# TRV_CC110L_V1_0.net
KiCad netlist of a schematic drawn in EAGLE
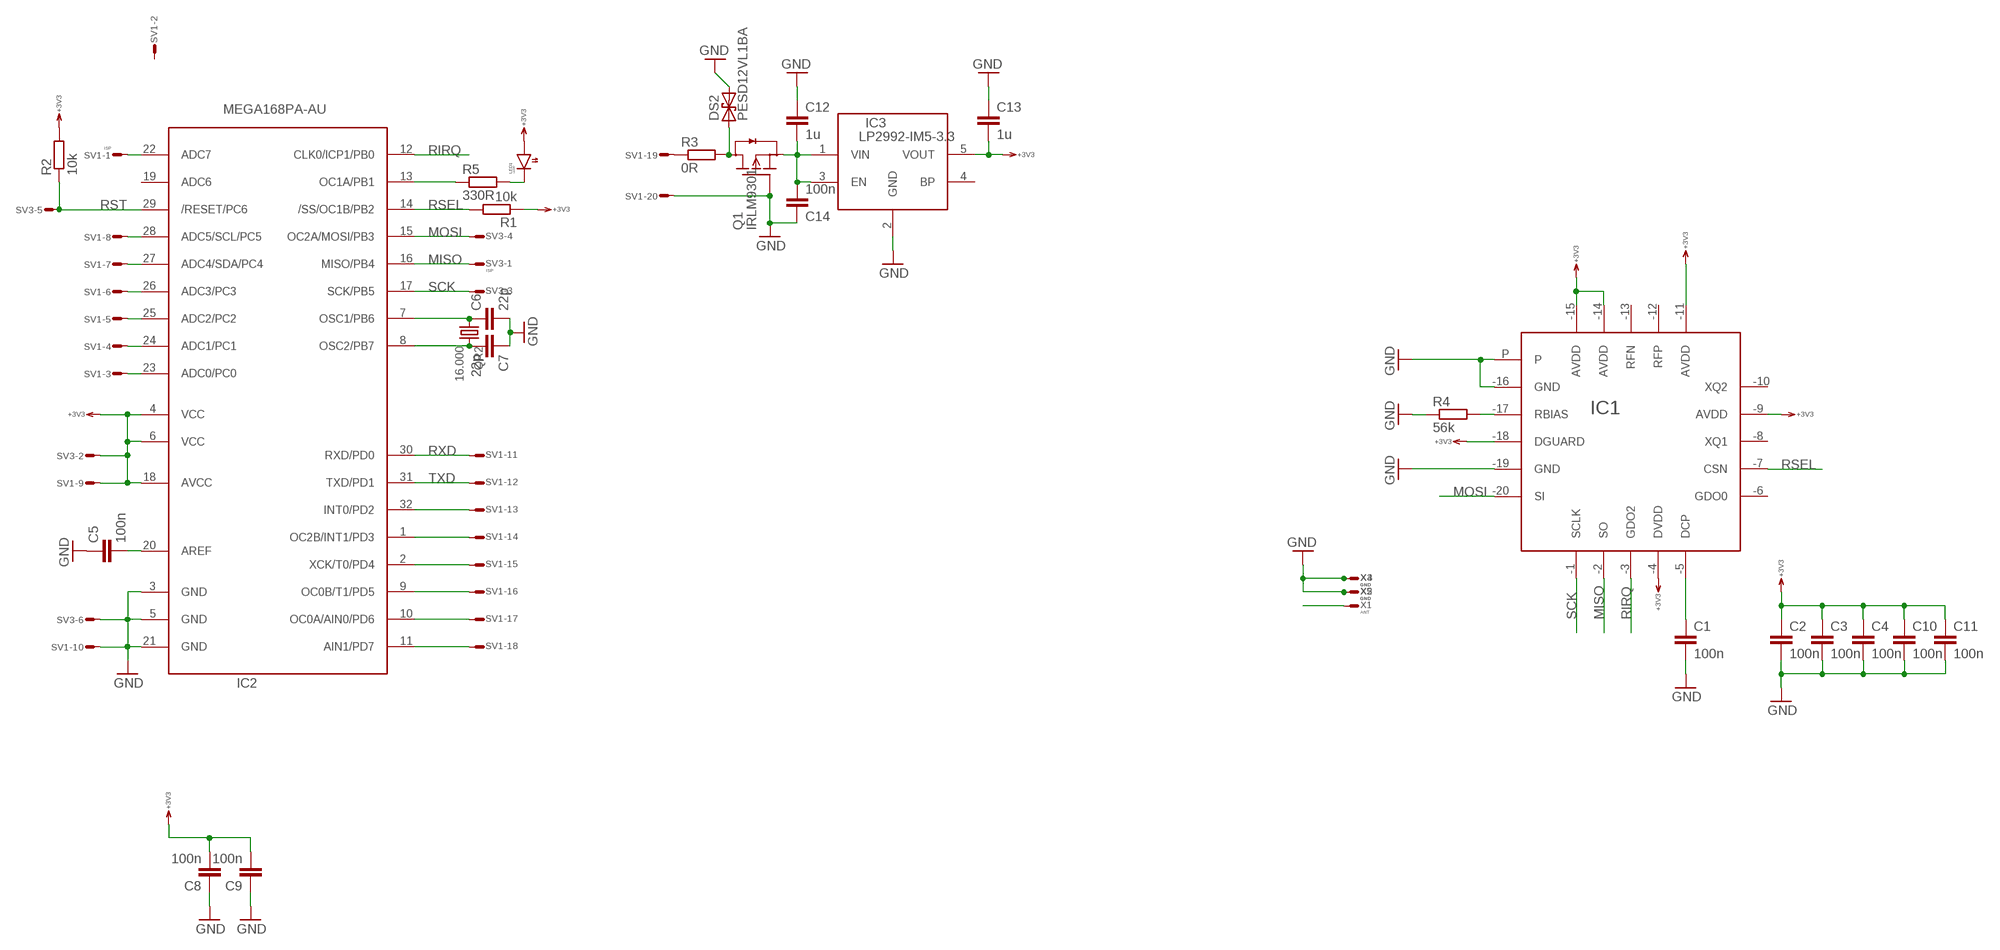
[diagram p0: schematic, sheet 1]

(export (version "E")
  (design (tool "Eeschema 10.0.6"))
  (components
    (comp (ref "C1")
      (value "100n")
      (footprint "eagle-import:0402")
      (libsource (lib "eagle-import") (part "C0402"))
    )
    (comp (ref "C2")
      (value "100n")
      (footprint "eagle-import:0603")
      (libsource (lib "eagle-import") (part "C0603"))
    )
    (comp (ref "C3")
      (value "100n")
      (footprint "eagle-import:0402")
      (libsource (lib "eagle-import") (part "C0402"))
    )
    (comp (ref "C4")
      (value "100n")
      (footprint "eagle-import:0402")
      (libsource (lib "eagle-import") (part "C0402"))
    )
    (comp (ref "C5")
      (value "100n")
      (footprint "eagle-import:0603")
      (libsource (lib "eagle-import") (part "C0603"))
    )
    (comp (ref "C6")
      (value "22p")
      (footprint "eagle-import:0603")
      (libsource (lib "eagle-import") (part "C0603"))
    )
    (comp (ref "C7")
      (value "22p")
      (footprint "eagle-import:0603")
      (libsource (lib "eagle-import") (part "C0603"))
    )
    (comp (ref "C8")
      (value "100n")
      (footprint "eagle-import:0603")
      (libsource (lib "eagle-import") (part "C0603"))
    )
    (comp (ref "C9")
      (value "100n")
      (footprint "eagle-import:0603")
      (libsource (lib "eagle-import") (part "C0603"))
    )
    (comp (ref "C10")
      (value "100n")
      (footprint "eagle-import:0402")
      (libsource (lib "eagle-import") (part "C0402"))
    )
    (comp (ref "C11")
      (value "100n")
      (footprint "eagle-import:0402")
      (libsource (lib "eagle-import") (part "C0402"))
    )
    (comp (ref "C12")
      (value "1u")
      (footprint "eagle-import:0603")
      (libsource (lib "eagle-import") (part "C0603"))
    )
    (comp (ref "C13")
      (value "1u")
      (footprint "eagle-import:0603")
      (libsource (lib "eagle-import") (part "C0603"))
    )
    (comp (ref "C14")
      (value "100n")
      (footprint "eagle-import:0603")
      (libsource (lib "eagle-import") (part "C0603"))
    )
    (comp (ref "DS2")
      (value "PESD12VL1BA")
      (footprint "eagle-import:SOD323")
      (libsource (lib "eagle-import") (part "TVS-U323"))
    )
    (comp (ref "IC1")
      (value "CC110L")
      (footprint "eagle-import:VQFN20")
      (libsource (lib "eagle-import") (part "CC110L"))
    )
    (comp (ref "IC2")
      (value "MEGA168PA-AU")
      (footprint "eagle-import:TQFP32-08")
      (libsource (lib "eagle-import") (part "MEGA168PA"))
    )
    (comp (ref "IC3")
      (value "LP2992-IM5-3.3")
      (footprint "eagle-import:SOT23-5")
      (libsource (lib "eagle-import") (part "LDO"))
    )
    (comp (ref "LED1")
      (value "LEDR")
      (footprint "eagle-import:0603")
      (libsource (lib "eagle-import") (part "LED0603"))
    )
    (comp (ref "Q1")
      (value "IRLM9301")
      (footprint "eagle-import:SOT23")
      (libsource (lib "eagle-import") (part "FET-PDSOT23"))
    )
    (comp (ref "QR2")
      (value "16.000")
      (footprint "eagle-import:HC49U-V")
      (libsource (lib "eagle-import") (part "Q49UV"))
    )
    (comp (ref "R1")
      (value "10k")
      (footprint "eagle-import:0603")
      (libsource (lib "eagle-import") (part "R0603"))
    )
    (comp (ref "R2")
      (value "10k")
      (footprint "eagle-import:0603")
      (libsource (lib "eagle-import") (part "R0603"))
    )
    (comp (ref "R3")
      (value "0R")
      (footprint "eagle-import:0603")
      (libsource (lib "eagle-import") (part "R0603"))
    )
    (comp (ref "R4")
      (value "56k")
      (footprint "eagle-import:0402")
      (libsource (lib "eagle-import") (part "R0402"))
    )
    (comp (ref "R5")
      (value "330R")
      (footprint "eagle-import:0603")
      (libsource (lib "eagle-import") (part "R0603"))
    )
    (comp (ref "SV1")
      (value "ISP")
      (footprint "eagle-import:ML20")
      (libsource (lib "eagle-import") (part "ML20?E"))
    )
    (comp (ref "SV3")
      (value "ISP")
      (footprint "eagle-import:ML6")
      (libsource (lib "eagle-import") (part "ML6E"))
    )
    (comp (ref "X1")
      (value "ANT")
      (footprint "eagle-import:S2.54_1.27")
      (libsource (lib "eagle-import") (part "WIREPADS2.54/1.27"))
    )
    (comp (ref "X2")
      (value "GND")
      (footprint "eagle-import:S2.54_1.27")
      (libsource (lib "eagle-import") (part "WIREPADS2.54/1.27"))
    )
    (comp (ref "X3")
      (value "GND")
      (footprint "eagle-import:S2.54_1.27")
      (libsource (lib "eagle-import") (part "WIREPADS2.54/1.27"))
    )
    (comp (ref "X4")
      (value "GND")
      (footprint "eagle-import:S2.54_1.27")
      (libsource (lib "eagle-import") (part "WIREPADS2.54/1.27"))
    )
    (comp (ref "X5")
      (value "GND")
      (footprint "eagle-import:S2.54_1.27")
      (libsource (lib "eagle-import") (part "WIREPADS2.54/1.27"))
    )
  )
  (nets
    (net (code "1") (name "+3V3") (class "Default")
      (node (ref "C10") (pin "1") (pinfunction "1_1") (pintype "passive"))
      (node (ref "C11") (pin "1") (pinfunction "1_1") (pintype "passive"))
      (node (ref "C13") (pin "2") (pinfunction "2_2") (pintype "passive"))
      (node (ref "C2") (pin "1") (pinfunction "1_1") (pintype "passive"))
      (node (ref "C3") (pin "1") (pinfunction "1_1") (pintype "passive"))
      (node (ref "C4") (pin "1") (pinfunction "1_1") (pintype "passive"))
      (node (ref "C8") (pin "2") (pinfunction "2_2") (pintype "passive"))
      (node (ref "C9") (pin "2") (pinfunction "2_2") (pintype "passive"))
      (node (ref "IC1") (pin "-11") (pinfunction "AVDD_-11") (pintype "bidirectional"))
      (node (ref "IC1") (pin "-14") (pinfunction "AVDD_-14") (pintype "bidirectional"))
      (node (ref "IC1") (pin "-15") (pinfunction "AVDD_-15") (pintype "bidirectional"))
      (node (ref "IC1") (pin "-18") (pinfunction "DGUARD_-18") (pintype "bidirectional"))
      (node (ref "IC1") (pin "-4") (pinfunction "DVDD_-4") (pintype "bidirectional"))
      (node (ref "IC1") (pin "-9") (pinfunction "AVDD_-9") (pintype "bidirectional"))
      (node (ref "IC2") (pin "18") (pinfunction "AVCC_18") (pintype "bidirectional"))
      (node (ref "IC2") (pin "4") (pinfunction "VCC_4") (pintype "bidirectional"))
      (node (ref "IC2") (pin "6") (pinfunction "VCC_6") (pintype "bidirectional"))
      (node (ref "IC3") (pin "5") (pinfunction "VOUT_5") (pintype "bidirectional"))
      (node (ref "LED1") (pin "1") (pinfunction "A_1") (pintype "bidirectional"))
      (node (ref "R1") (pin "1") (pinfunction "1_1") (pintype "passive"))
      (node (ref "R2") (pin "2") (pinfunction "2_2") (pintype "passive"))
      (node (ref "SV1") (pin "9") (pinfunction "S_9") (pintype "passive"))
      (node (ref "SV3") (pin "2") (pinfunction "S_2") (pintype "passive"))
    )
    (net (code "2") (name "/MISO") (class "Default")
      (node (ref "IC1") (pin "-2") (pinfunction "SO_-2") (pintype "output"))
      (node (ref "IC2") (pin "16") (pinfunction "MISO/PB4_16") (pintype "bidirectional"))
      (node (ref "SV3") (pin "1") (pinfunction "S_1") (pintype "passive"))
    )
    (net (code "3") (name "/MOSI") (class "Default")
      (node (ref "IC1") (pin "-20") (pinfunction "SI_-20") (pintype "input"))
      (node (ref "IC2") (pin "15") (pinfunction "OC2A/MOSI/PB3_15") (pintype "bidirectional"))
      (node (ref "SV3") (pin "4") (pinfunction "S_4") (pintype "passive"))
    )
    (net (code "4") (name "/RIRQ") (class "Default")
      (node (ref "IC1") (pin "-3") (pinfunction "GDO2_-3") (pintype "output"))
      (node (ref "IC2") (pin "12") (pinfunction "CLK0/ICP1/PB0_12") (pintype "bidirectional"))
    )
    (net (code "5") (name "/RSEL") (class "Default")
      (node (ref "IC1") (pin "-7") (pinfunction "CSN_-7") (pintype "input"))
      (node (ref "IC2") (pin "14") (pinfunction "/SS/OC1B/PB2_14") (pintype "bidirectional"))
      (node (ref "R1") (pin "2") (pinfunction "2_2") (pintype "passive"))
    )
    (net (code "6") (name "/RST") (class "Default")
      (node (ref "IC2") (pin "29") (pinfunction "/RESET/PC6_29") (pintype "bidirectional"))
      (node (ref "R2") (pin "1") (pinfunction "1_1") (pintype "passive"))
      (node (ref "SV3") (pin "5") (pinfunction "S_5") (pintype "passive"))
    )
    (net (code "7") (name "/RXD") (class "Default")
      (node (ref "IC2") (pin "30") (pinfunction "RXD/PD0_30") (pintype "bidirectional"))
      (node (ref "SV1") (pin "11") (pinfunction "S_11") (pintype "passive"))
    )
    (net (code "8") (name "/SCK") (class "Default")
      (node (ref "IC1") (pin "-1") (pinfunction "SCLK_-1") (pintype "input"))
      (node (ref "IC2") (pin "17") (pinfunction "SCK/PB5_17") (pintype "bidirectional"))
      (node (ref "SV3") (pin "3") (pinfunction "S_3") (pintype "passive"))
    )
    (net (code "9") (name "/TXD") (class "Default")
      (node (ref "IC2") (pin "31") (pinfunction "TXD/PD1_31") (pintype "bidirectional"))
      (node (ref "SV1") (pin "12") (pinfunction "S_12") (pintype "passive"))
    )
    (net (code "10") (name "GND") (class "Default")
      (node (ref "C1") (pin "2") (pinfunction "2_2") (pintype "passive"))
      (node (ref "C10") (pin "2") (pinfunction "2_2") (pintype "passive"))
      (node (ref "C11") (pin "2") (pinfunction "2_2") (pintype "passive"))
      (node (ref "C12") (pin "1") (pinfunction "1_1") (pintype "passive"))
      (node (ref "C13") (pin "1") (pinfunction "1_1") (pintype "passive"))
      (node (ref "C14") (pin "1") (pinfunction "1_1") (pintype "passive"))
      (node (ref "C2") (pin "2") (pinfunction "2_2") (pintype "passive"))
      (node (ref "C3") (pin "2") (pinfunction "2_2") (pintype "passive"))
      (node (ref "C4") (pin "2") (pinfunction "2_2") (pintype "passive"))
      (node (ref "C5") (pin "1") (pinfunction "1_1") (pintype "passive"))
      (node (ref "C6") (pin "2") (pinfunction "2_2") (pintype "passive"))
      (node (ref "C7") (pin "1") (pinfunction "1_1") (pintype "passive"))
      (node (ref "C8") (pin "1") (pinfunction "1_1") (pintype "passive"))
      (node (ref "C9") (pin "1") (pinfunction "1_1") (pintype "passive"))
      (node (ref "DS2") (pin "C") (pinfunction "2_C") (pintype "passive"))
      (node (ref "IC1") (pin "-16") (pinfunction "GND_-16") (pintype "bidirectional"))
      (node (ref "IC1") (pin "-19") (pinfunction "GND_-19") (pintype "bidirectional"))
      (node (ref "IC1") (pin "P") (pinfunction "P_P") (pintype "bidirectional"))
      (node (ref "IC2") (pin "21") (pinfunction "GND_21") (pintype "bidirectional"))
      (node (ref "IC2") (pin "3") (pinfunction "GND_3") (pintype "bidirectional"))
      (node (ref "IC2") (pin "5") (pinfunction "GND_5") (pintype "bidirectional"))
      (node (ref "IC3") (pin "2") (pinfunction "GND_2") (pintype "bidirectional"))
      (node (ref "Q1") (pin "1") (pinfunction "G_1") (pintype "passive"))
      (node (ref "R4") (pin "1") (pinfunction "1_1") (pintype "passive"))
      (node (ref "SV1") (pin "10") (pinfunction "S_10") (pintype "passive"))
      (node (ref "SV1") (pin "20") (pinfunction "S_20") (pintype "passive"))
      (node (ref "SV3") (pin "6") (pinfunction "S_6") (pintype "passive"))
      (node (ref "X2") (pin "1") (pinfunction "S_1") (pintype "passive"))
      (node (ref "X3") (pin "1") (pinfunction "S_1") (pintype "passive"))
      (node (ref "X4") (pin "1") (pinfunction "S_1") (pintype "passive"))
      (node (ref "X5") (pin "1") (pinfunction "S_1") (pintype "passive"))
    )
    (net (code "11") (name "Net-(DS2-1)") (class "Default")
      (node (ref "DS2") (pin "A") (pinfunction "1_A") (pintype "passive"))
      (node (ref "Q1") (pin "3") (pinfunction "D_3") (pintype "passive"))
      (node (ref "R3") (pin "2") (pinfunction "2_2") (pintype "passive"))
    )
    (net (code "12") (name "Net-(IC1-DCP)") (class "Default")
      (node (ref "C1") (pin "1") (pinfunction "1_1") (pintype "passive"))
      (node (ref "IC1") (pin "-5") (pinfunction "DCP_-5") (pintype "bidirectional"))
    )
    (net (code "13") (name "Net-(IC1-RBIAS)") (class "Default")
      (node (ref "IC1") (pin "-17") (pinfunction "RBIAS_-17") (pintype "bidirectional"))
      (node (ref "R4") (pin "2") (pinfunction "2_2") (pintype "passive"))
    )
    (net (code "14") (name "Net-(IC2-ADC0{slash}PC0)") (class "Default")
      (node (ref "IC2") (pin "23") (pinfunction "ADC0/PC0_23") (pintype "bidirectional"))
      (node (ref "SV1") (pin "3") (pinfunction "S_3") (pintype "passive"))
    )
    (net (code "15") (name "Net-(IC2-ADC1{slash}PC1)") (class "Default")
      (node (ref "IC2") (pin "24") (pinfunction "ADC1/PC1_24") (pintype "bidirectional"))
      (node (ref "SV1") (pin "4") (pinfunction "S_4") (pintype "passive"))
    )
    (net (code "16") (name "Net-(IC2-ADC2{slash}PC2)") (class "Default")
      (node (ref "IC2") (pin "25") (pinfunction "ADC2/PC2_25") (pintype "bidirectional"))
      (node (ref "SV1") (pin "5") (pinfunction "S_5") (pintype "passive"))
    )
    (net (code "17") (name "Net-(IC2-ADC3{slash}PC3)") (class "Default")
      (node (ref "IC2") (pin "26") (pinfunction "ADC3/PC3_26") (pintype "bidirectional"))
      (node (ref "SV1") (pin "6") (pinfunction "S_6") (pintype "passive"))
    )
    (net (code "18") (name "Net-(IC2-ADC4{slash}SDA{slash}PC4)") (class "Default")
      (node (ref "IC2") (pin "27") (pinfunction "ADC4/SDA/PC4_27") (pintype "bidirectional"))
      (node (ref "SV1") (pin "7") (pinfunction "S_7") (pintype "passive"))
    )
    (net (code "19") (name "Net-(IC2-ADC5{slash}SCL{slash}PC5)") (class "Default")
      (node (ref "IC2") (pin "28") (pinfunction "ADC5/SCL/PC5_28") (pintype "bidirectional"))
      (node (ref "SV1") (pin "8") (pinfunction "S_8") (pintype "passive"))
    )
    (net (code "20") (name "Net-(IC2-ADC7)") (class "Default")
      (node (ref "IC2") (pin "22") (pinfunction "ADC7_22") (pintype "bidirectional"))
      (node (ref "SV1") (pin "1") (pinfunction "S_1") (pintype "passive"))
    )
    (net (code "21") (name "Net-(IC2-AIN1{slash}PD7)") (class "Default")
      (node (ref "IC2") (pin "11") (pinfunction "AIN1/PD7_11") (pintype "bidirectional"))
      (node (ref "SV1") (pin "18") (pinfunction "S_18") (pintype "passive"))
    )
    (net (code "22") (name "Net-(IC2-AREF)") (class "Default")
      (node (ref "C5") (pin "2") (pinfunction "2_2") (pintype "passive"))
      (node (ref "IC2") (pin "20") (pinfunction "AREF_20") (pintype "bidirectional"))
    )
    (net (code "23") (name "Net-(IC2-INT0{slash}PD2)") (class "Default")
      (node (ref "IC2") (pin "32") (pinfunction "INT0/PD2_32") (pintype "bidirectional"))
      (node (ref "SV1") (pin "13") (pinfunction "S_13") (pintype "passive"))
    )
    (net (code "24") (name "Net-(IC2-OC0A{slash}AIN0{slash}PD6)") (class "Default")
      (node (ref "IC2") (pin "10") (pinfunction "OC0A/AIN0/PD6_10") (pintype "bidirectional"))
      (node (ref "SV1") (pin "17") (pinfunction "S_17") (pintype "passive"))
    )
    (net (code "25") (name "Net-(IC2-OC0B{slash}T1{slash}PD5)") (class "Default")
      (node (ref "IC2") (pin "9") (pinfunction "OC0B/T1/PD5_9") (pintype "bidirectional"))
      (node (ref "SV1") (pin "16") (pinfunction "S_16") (pintype "passive"))
    )
    (net (code "26") (name "Net-(IC2-OC1A{slash}PB1)") (class "Default")
      (node (ref "IC2") (pin "13") (pinfunction "OC1A/PB1_13") (pintype "bidirectional"))
      (node (ref "R5") (pin "1") (pinfunction "1_1") (pintype "passive"))
    )
    (net (code "27") (name "Net-(IC2-OC2B{slash}INT1{slash}PD3)") (class "Default")
      (node (ref "IC2") (pin "1") (pinfunction "OC2B/INT1/PD3_1") (pintype "bidirectional"))
      (node (ref "SV1") (pin "14") (pinfunction "S_14") (pintype "passive"))
    )
    (net (code "28") (name "Net-(IC2-OSC1{slash}PB6)") (class "Default")
      (node (ref "C6") (pin "1") (pinfunction "1_1") (pintype "passive"))
      (node (ref "IC2") (pin "7") (pinfunction "OSC1/PB6_7") (pintype "bidirectional"))
      (node (ref "QR2") (pin "1") (pinfunction "1_1") (pintype "passive"))
    )
    (net (code "29") (name "Net-(IC2-OSC2{slash}PB7)") (class "Default")
      (node (ref "C7") (pin "2") (pinfunction "2_2") (pintype "passive"))
      (node (ref "IC2") (pin "8") (pinfunction "OSC2/PB7_8") (pintype "bidirectional"))
      (node (ref "QR2") (pin "2") (pinfunction "2_2") (pintype "passive"))
    )
    (net (code "30") (name "Net-(IC2-XCK{slash}T0{slash}PD4)") (class "Default")
      (node (ref "IC2") (pin "2") (pinfunction "XCK/T0/PD4_2") (pintype "bidirectional"))
      (node (ref "SV1") (pin "15") (pinfunction "S_15") (pintype "passive"))
    )
    (net (code "31") (name "Net-(IC3-EN)") (class "Default")
      (node (ref "C12") (pin "2") (pinfunction "2_2") (pintype "passive"))
      (node (ref "C14") (pin "2") (pinfunction "2_2") (pintype "passive"))
      (node (ref "IC3") (pin "1") (pinfunction "VIN_1") (pintype "bidirectional"))
      (node (ref "IC3") (pin "3") (pinfunction "EN_3") (pintype "bidirectional"))
      (node (ref "Q1") (pin "2") (pinfunction "S_2") (pintype "passive"))
    )
    (net (code "32") (name "Net-(LED1-C)") (class "Default")
      (node (ref "LED1") (pin "2") (pinfunction "C_2") (pintype "bidirectional"))
      (node (ref "R5") (pin "2") (pinfunction "2_2") (pintype "passive"))
    )
    (net (code "33") (name "Net-(SV1K-S)") (class "Default")
      (node (ref "R3") (pin "1") (pinfunction "1_1") (pintype "passive"))
      (node (ref "SV1") (pin "19") (pinfunction "S_19") (pintype "passive"))
    )
    (net (code "34") (name "unconnected-(IC1-GDO0-Pad-6)") (class "Default")
      (node (ref "IC1") (pin "-6") (pinfunction "GDO0_-6") (pintype "bidirectional"))
    )
    (net (code "35") (name "unconnected-(IC1-RFN-Pad-13)") (class "Default")
      (node (ref "IC1") (pin "-13") (pinfunction "RFN_-13") (pintype "bidirectional"))
    )
    (net (code "36") (name "unconnected-(IC1-RFP-Pad-12)") (class "Default")
      (node (ref "IC1") (pin "-12") (pinfunction "RFP_-12") (pintype "bidirectional"))
    )
    (net (code "37") (name "unconnected-(IC1-XQ1-Pad-8)") (class "Default")
      (node (ref "IC1") (pin "-8") (pinfunction "XQ1_-8") (pintype "bidirectional"))
    )
    (net (code "38") (name "unconnected-(IC1-XQ2-Pad-10)") (class "Default")
      (node (ref "IC1") (pin "-10") (pinfunction "XQ2_-10") (pintype "bidirectional"))
    )
    (net (code "39") (name "unconnected-(IC2-ADC6-Pad19)") (class "Default")
      (node (ref "IC2") (pin "19") (pinfunction "ADC6_19") (pintype "bidirectional"))
    )
    (net (code "40") (name "unconnected-(IC3-BP-Pad4)") (class "Default")
      (node (ref "IC3") (pin "4") (pinfunction "BP_4") (pintype "bidirectional"))
    )
    (net (code "41") (name "unconnected-(SV1L-S-Pad2)") (class "Default")
      (node (ref "SV1") (pin "2") (pinfunction "S_2") (pintype "passive"))
    )
    (net (code "42") (name "unconnected-(X1-S-Pad1)") (class "Default")
      (node (ref "X1") (pin "1") (pinfunction "S_1") (pintype "passive"))
    )
  )
)
